# LastSchema.net
KiCad netlist of a schematic drawn in Altium Designer
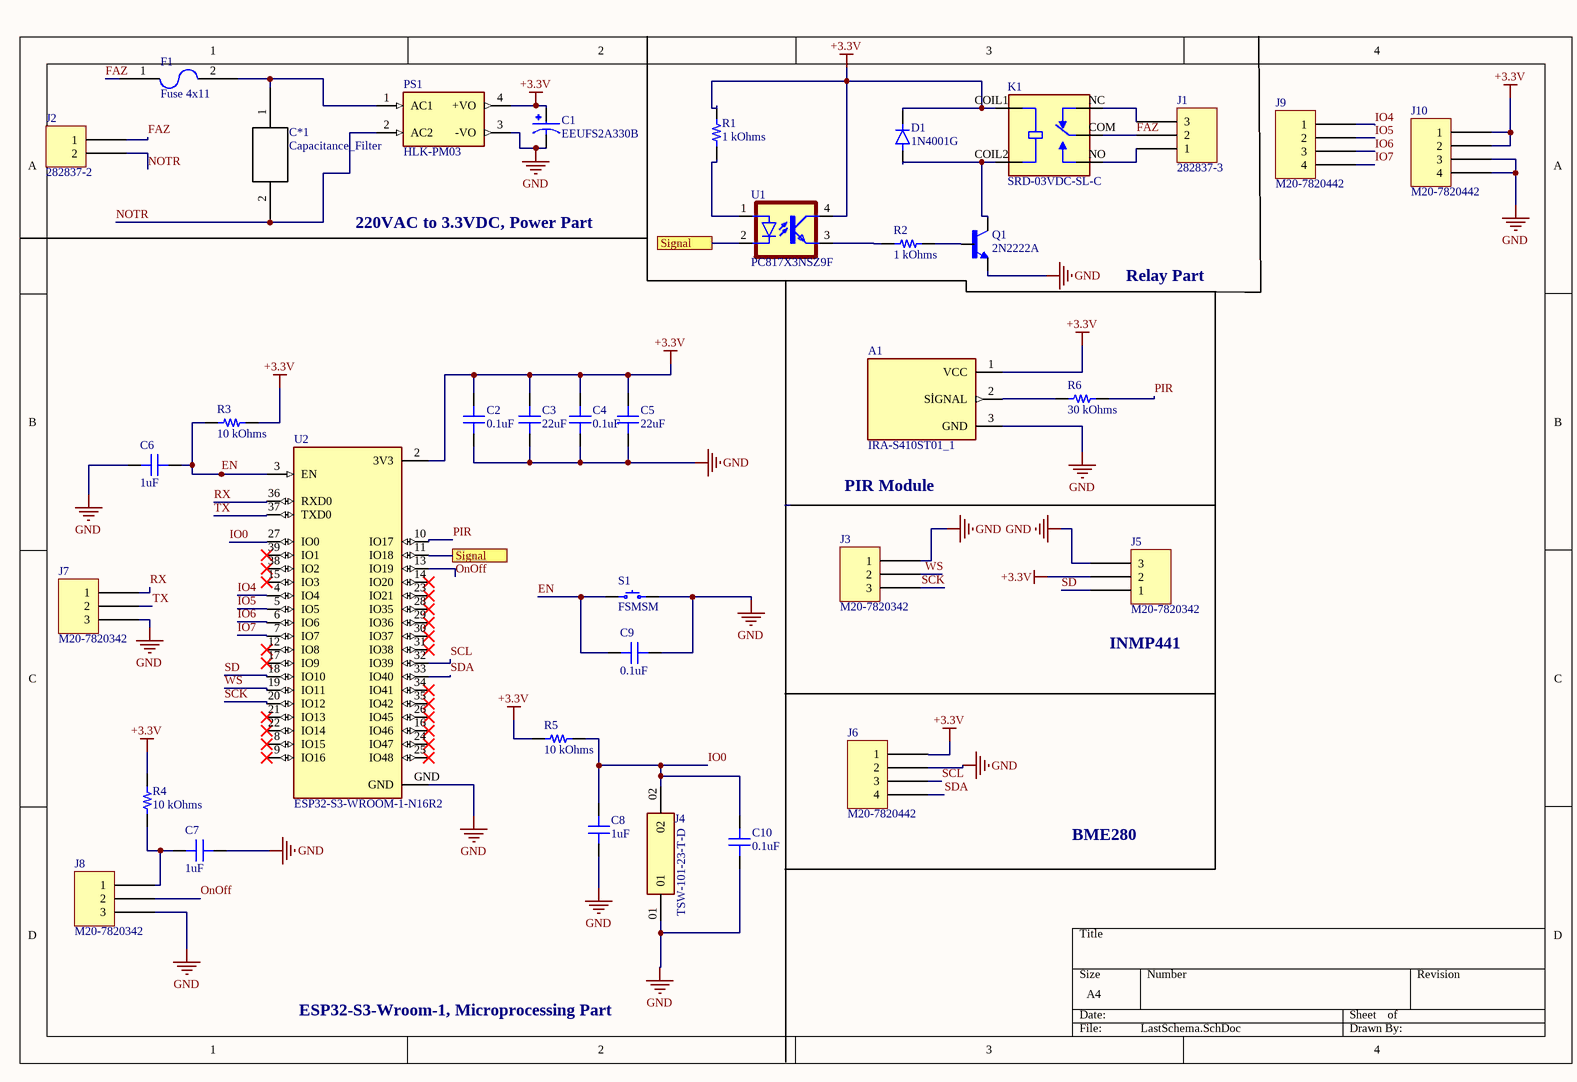
[diagram p0: LastSchema.SchDoc]

(export (version "E")
  (design (tool "Eeschema 10.0.6"))
  (components
    (comp (ref "A1")
      (value "IRA-S410ST01_1")
      (footprint "TO254P940H490-3 - duplicate")
      (description "Sensor PIR (Passive Infrared) Motion Sensing Radial, Metal Can, Lensed - 3 Lead")
      (fields (field (name "MP") "IRA-S410ST01") (field (name "MF") "Murata"))
      (libsource (lib "Integrated_Library1") (part "IRA-S410ST01_1"))
    )
    (comp (ref "C*1")
      (value "Capacitance_Filter")
      (footprint "Capacitance_Filter")
      (libsource (lib "Integrated_Library1") (part "Capacitance_Filter"))
    )
    (comp (ref "C1")
      (value "EEUFS2A330B")
      (footprint "CAPPRD500W60D800H1150")
      (description "CAP ALUM 33UF 20% 100V THRU HOLE")
      (fields (field (name "MF") "Panasonic"))
      (libsource (lib "Integrated_Library1") (part "EEUFS2A330B"))
    )
    (comp (ref "C2")
      (value "1 µF")
      (footprint "CAP 0603_1608")
      (description "CAP CER 1UF 16V X7R 0603")
      (fields
        (field (name "PART NUMBER") "C0603C105K4RACAUTO")
        (field (name "CAPACITANCE") "0.1uF")
        (field (name "MANUFACTURER") "KEMET")
      )
      (libsource (lib "Celestial Altium Library - altium_library") (part "Capacitor"))
    )
    (comp (ref "C3")
      (value "1 µF")
      (footprint "CAP 0603_1608")
      (description "CAP CER 1UF 16V X7R 0603")
      (fields
        (field (name "PART NUMBER") "C0603C105K4RACAUTO")
        (field (name "CAPACITANCE") "22uF")
        (field (name "MANUFACTURER") "KEMET")
      )
      (libsource (lib "Celestial Altium Library - altium_library") (part "Capacitor"))
    )
    (comp (ref "C4")
      (value "1 µF")
      (footprint "CAP 0603_1608")
      (description "CAP CER 1UF 16V X7R 0603")
      (fields
        (field (name "PART NUMBER") "C0603C105K4RACAUTO")
        (field (name "CAPACITANCE") "0.1uF")
        (field (name "MANUFACTURER") "KEMET")
      )
      (libsource (lib "Celestial Altium Library - altium_library") (part "Capacitor"))
    )
    (comp (ref "C5")
      (value "1 µF")
      (footprint "CAP 0603_1608")
      (description "CAP CER 1UF 16V X7R 0603")
      (fields
        (field (name "PART NUMBER") "C0603C105K4RACAUTO")
        (field (name "CAPACITANCE") "22uF")
        (field (name "MANUFACTURER") "KEMET")
      )
      (libsource (lib "Celestial Altium Library - altium_library") (part "Capacitor"))
    )
    (comp (ref "C6")
      (value "1 µF")
      (footprint "CAP 0603_1608")
      (description "CAP CER 1UF 16V X7R 0603")
      (fields
        (field (name "PART NUMBER") "C0603C105K4RACAUTO")
        (field (name "CAPACITANCE") "1uF")
        (field (name "MANUFACTURER") "KEMET")
      )
      (libsource (lib "Celestial Altium Library - altium_library") (part "Capacitor"))
    )
    (comp (ref "C7")
      (value "1 µF")
      (footprint "CAP 0603_1608")
      (description "CAP CER 1UF 16V X7R 0603")
      (fields
        (field (name "PART NUMBER") "C0603C105K4RACAUTO")
        (field (name "CAPACITANCE") "1uF")
        (field (name "MANUFACTURER") "KEMET")
      )
      (libsource (lib "Celestial Altium Library - altium_library") (part "Capacitor"))
    )
    (comp (ref "C8")
      (value "1 µF")
      (footprint "CAP 0603_1608")
      (description "CAP CER 1UF 16V X7R 0603")
      (fields
        (field (name "PART NUMBER") "C0603C105K4RACAUTO")
        (field (name "CAPACITANCE") "1uF")
        (field (name "MANUFACTURER") "KEMET")
      )
      (libsource (lib "Celestial Altium Library - altium_library") (part "Capacitor"))
    )
    (comp (ref "C9")
      (value "1 µF")
      (footprint "CAP 0603_1608")
      (description "CAP CER 1UF 16V X7R 0603")
      (fields
        (field (name "PART NUMBER") "C0603C105K4RACAUTO")
        (field (name "CAPACITANCE") "0.1uF")
        (field (name "MANUFACTURER") "KEMET")
      )
      (libsource (lib "Celestial Altium Library - altium_library") (part "Capacitor"))
    )
    (comp (ref "C10")
      (value "1 µF")
      (footprint "CAP 0603_1608")
      (description "CAP CER 1UF 16V X7R 0603")
      (fields
        (field (name "PART NUMBER") "C0603C105K4RACAUTO")
        (field (name "CAPACITANCE") "0.1uF")
        (field (name "MANUFACTURER") "KEMET")
      )
      (libsource (lib "Celestial Altium Library - altium_library") (part "Capacitor"))
    )
    (comp (ref "D1")
      (value "1N4001G")
      (footprint "DIOAD1036W78L470D235")
      (description "1A, 50V, Standard Recovery Rectifier")
      (fields (field (name "MF") "Taiwan Semiconductor"))
      (libsource (lib "Integrated_Library1") (part "1N4001G"))
    )
    (comp (ref "F1")
      (value "Fuse 4x11")
      (footprint "Fuse 4x11")
      (libsource (lib "Integrated_Library1") (part "Fuse 4x11"))
    )
    (comp (ref "J1")
      (value "282837-3")
      (footprint "TE 282837-3")
      (description "TERM BLK 3P SIDE ENT 5.08MM PCB")
      (fields (field (name "MANUFACTURER") "TE Connectivity AMP Connectors") (field (name "VOLTAGE") "300 V"))
      (libsource (lib "Celestial Altium Library - altium_library") (part "3 Pin"))
    )
    (comp (ref "J2")
      (value "282837-2")
      (footprint "TE 282837-2")
      (description "TERM BLK 2P SIDE ENT 5.08MM PCB")
      (fields (field (name "MANUFACTURER") "TE Connectivity AMP Connectors") (field (name "VOLTAGE") "300 V"))
      (libsource (lib "Celestial Altium Library - altium_library") (part "2 Pin"))
    )
    (comp (ref "J3")
      (value "M20-7820342")
      (footprint "HARWIN M20-7820345")
      (description "CONN RCPT 3POS 0.1 GOLD PCB")
      (fields (field (name "MANUFACTURER") "Harwin Inc."))
      (libsource (lib "") (part "3 Pin_1"))
    )
    (comp (ref "J4")
      (value "TSW-101-23-T-D")
      (footprint "SAMTEC_TSW-101-23-T-D")
      (description "TSW Series .100 Terminal Strip")
      (fields (field (name "MF") "Samtec"))
      (libsource (lib "Integrated_Library1") (part "TSW-101-23-T-D"))
    )
    (comp (ref "J5")
      (value "M20-7820342")
      (footprint "HARWIN M20-7820345")
      (description "CONN RCPT 3POS 0.1 GOLD PCB")
      (fields (field (name "MANUFACTURER") "Harwin Inc."))
      (libsource (lib "Celestial Altium Library - altium_library") (part "3 Pin"))
    )
    (comp (ref "J6")
      (value "M20-7820442")
      (footprint "HARWIN M20-7820445")
      (description "CONN RCPT 4POS 0.1 GOLD PCB")
      (fields (field (name "MANUFACTURER") "Harwin Inc."))
      (libsource (lib "Celestial Altium Library - altium_library") (part "4 Pin"))
    )
    (comp (ref "J7")
      (value "M20-7820342")
      (footprint "HARWIN M20-7820345")
      (description "CONN RCPT 3POS 0.1 GOLD PCB")
      (fields (field (name "MANUFACTURER") "Harwin Inc."))
      (libsource (lib "") (part "3 Pin_1"))
    )
    (comp (ref "J8")
      (value "M20-7820342")
      (footprint "HARWIN M20-7820345")
      (description "CONN RCPT 3POS 0.1 GOLD PCB")
      (fields (field (name "MANUFACTURER") "Harwin Inc."))
      (libsource (lib "") (part "3 Pin_1"))
    )
    (comp (ref "J9")
      (value "M20-7820442")
      (footprint "HARWIN M20-7820445")
      (description "CONN RCPT 4POS 0.1 GOLD PCB")
      (fields (field (name "MANUFACTURER") "Harwin Inc."))
      (libsource (lib "Celestial Altium Library - altium_library") (part "4 Pin"))
    )
    (comp (ref "J10")
      (value "M20-7820442")
      (footprint "HARWIN M20-7820445")
      (description "CONN RCPT 4POS 0.1 GOLD PCB")
      (fields (field (name "MANUFACTURER") "Harwin Inc."))
      (libsource (lib "Celestial Altium Library - altium_library") (part "4 Pin"))
    )
    (comp (ref "K1")
      (value "SRD-03VDC-SL-C")
      (footprint "RELAY_SRD-03VDC-SL-C")
      (description "Relays General Purpose Non Latching 3VDC SPDT 10A (250VAC) Max 5PIN")
      (fields (field (name "MF") "Songle Relay"))
      (libsource (lib "Integrated_Library1") (part "SRD-03VDC-SL-C"))
    )
    (comp (ref "PS1")
      (value "HLK-PM03")
      (footprint "CONV_HLK-PM03")
      (fields (field (name "MF") "Hi-link"))
      (libsource (lib "Integrated_Library1") (part "HLK-PM03"))
    )
    (comp (ref "Q1")
      (value "2N2222A")
      (footprint "TO92254P470H750-3")
      (description "Bipolar (BJT) Transistor NPN 40 V 600 mA 250MHz 625 mW Through Hole TO-92")
      (fields (field (name "MF") "Diotec Semiconductor"))
      (libsource (lib "Integrated_Library1") (part "2N2222A"))
    )
    (comp (ref "R1")
      (value "1 kOhms")
      (footprint "RES 0603_1608")
      (description "RES SMD 46.4K OHM 0.5% 1/5W 0603")
      (fields
        (field (name "PART NUMBER") "ERJ-PB3D4642V")
        (field (name "MANUFACTURER") "Panasonic Electronic Components")
      )
      (libsource (lib "Celestial Altium Library - altium_library") (part "Resistor"))
    )
    (comp (ref "R2")
      (value "1 kOhms")
      (footprint "RES 0603_1608")
      (description "RES SMD 46.4K OHM 0.5% 1/5W 0603")
      (fields
        (field (name "PART NUMBER") "ERJ-PB3D4642V")
        (field (name "MANUFACTURER") "Panasonic Electronic Components")
      )
      (libsource (lib "Celestial Altium Library - altium_library") (part "Resistor"))
    )
    (comp (ref "R3")
      (value "10 kOhms")
      (footprint "RES 0603_1608")
      (description "RES SMD 46.4K OHM 0.5% 1/5W 0603")
      (fields
        (field (name "PART NUMBER") "ERJ-PB3D4642V")
        (field (name "MANUFACTURER") "Panasonic Electronic Components")
      )
      (libsource (lib "Celestial Altium Library - altium_library") (part "Resistor"))
    )
    (comp (ref "R4")
      (value "10 kOhms")
      (footprint "RES 0603_1608")
      (description "RES SMD 46.4K OHM 0.5% 1/5W 0603")
      (fields
        (field (name "PART NUMBER") "ERJ-PB3D4642V")
        (field (name "MANUFACTURER") "Panasonic Electronic Components")
      )
      (libsource (lib "Celestial Altium Library - altium_library") (part "Resistor"))
    )
    (comp (ref "R5")
      (value "10 kOhms")
      (footprint "RES 0603_1608")
      (description "RES SMD 46.4K OHM 0.5% 1/5W 0603")
      (fields
        (field (name "PART NUMBER") "ERJ-PB3D4642V")
        (field (name "MANUFACTURER") "Panasonic Electronic Components")
      )
      (libsource (lib "Celestial Altium Library - altium_library") (part "Resistor"))
    )
    (comp (ref "R6")
      (value "30 kOhms")
      (footprint "RES 0603_1608")
      (description "RES 10K OHM 0.1% 1/16W 0603")
      (fields
        (field (name "PART NUMBER") "RNCS0603BKE10K0")
        (field (name "MANUFACTURER") "Stackpole Electronics Inc")
      )
      (libsource (lib "Celestial Altium Library - altium_library") (part "Resistor"))
    )
    (comp (ref "S1")
      (value "FSMSM")
      (footprint "TE FSMSMTR")
      (description "SWITCH TACTILE SPST-NO 0.05A 24V")
      (fields (field (name "MANUFACTURER") "TE Connectivity ALCOSWITCH Switches"))
      (libsource (lib "Celestial Altium Library - altium_library") (part "SPST-NO 2 PIN"))
    )
    (comp (ref "U1")
      (value "PC817X3NSZ9F")
      (footprint "DIL04")
      (description "Optoisolator Transistor Output 5000Vrms 1 Channel 4-DIP")
      (fields (field (name "MF") "Sharp Microelectronics"))
      (libsource (lib "Integrated_Library1") (part "PC817X3NSZ9F"))
    )
    (comp (ref "U2")
      (value "ESP32-S3-WROOM-1-N16R2")
      (footprint "XCVR_ESP32-S3-WROOM-1-N16R2")
      (description "Bluetooth, WiFi 802.11b/g/n, Bluetooth v5.0 Transceiver Module 2.4GHz PCB Trace Surface Mount")
      (fields (field (name "MF") "Espressif Systems") (field (name "MP") "ESP32S3WROOM1N16R2"))
      (libsource (lib "Integrated_Library1") (part "ESP32-S3-WROOM-1-N16R2"))
    )
  )
  (nets
    (net (code "1") (name "+3.3V") (class "Default")
      (node (ref "A1") (pin "1") (pinfunction "VCC_1") (pintype "power_in"))
      (node (ref "C1") (pin "P") (pinfunction "P_P") (pintype "passive"))
      (node (ref "C2") (pin "1") (pinfunction "1_1") (pintype "passive"))
      (node (ref "C3") (pin "1") (pinfunction "1_1") (pintype "passive"))
      (node (ref "C4") (pin "1") (pinfunction "1_1") (pintype "passive"))
      (node (ref "C5") (pin "1") (pinfunction "1_1") (pintype "passive"))
      (node (ref "D1") (pin "C") (pinfunction "K_C") (pintype "passive"))
      (node (ref "J10") (pin "1") (pinfunction "1_1") (pintype "passive"))
      (node (ref "J10") (pin "2") (pinfunction "2_2") (pintype "passive"))
      (node (ref "J5") (pin "2") (pinfunction "2_2") (pintype "passive"))
      (node (ref "J6") (pin "1") (pinfunction "1_1") (pintype "passive"))
      (node (ref "K1") (pin "COIL1") (pinfunction "COIL1_COIL1") (pintype "passive"))
      (node (ref "PS1") (pin "4") (pinfunction "+VO_4") (pintype "output"))
      (node (ref "R1") (pin "2") (pinfunction "2_2") (pintype "passive"))
      (node (ref "R3") (pin "1") (pinfunction "1_1") (pintype "passive"))
      (node (ref "R4") (pin "1") (pinfunction "1_1") (pintype "passive"))
      (node (ref "R5") (pin "2") (pinfunction "2_2") (pintype "passive"))
      (node (ref "U1") (pin "4") (pinfunction "COL_4") (pintype "passive"))
      (node (ref "U2") (pin "2") (pinfunction "3V3_2") (pintype "power_in"))
    )
    (net (code "2") (name "/EN") (class "Default")
      (node (ref "C6") (pin "2") (pinfunction "2_2") (pintype "passive"))
      (node (ref "C9") (pin "2") (pinfunction "2_2") (pintype "passive"))
      (node (ref "R3") (pin "2") (pinfunction "2_2") (pintype "passive"))
      (node (ref "S1") (pin "1") (pinfunction "1_1") (pintype "passive"))
      (node (ref "U2") (pin "3") (pinfunction "EN_3") (pintype "input"))
    )
    (net (code "3") (name "/FAZ") (class "Default")
      (node (ref "F1") (pin "1") (pintype "passive"))
      (node (ref "J1") (pin "2") (pinfunction "2_2") (pintype "passive"))
      (node (ref "J2") (pin "1") (pinfunction "1_1") (pintype "passive"))
      (node (ref "K1") (pin "COM") (pinfunction "COM_COM") (pintype "passive"))
    )
    (net (code "4") (name "/IO0") (class "Default")
      (node (ref "C10") (pin "1") (pinfunction "1_1") (pintype "passive"))
      (node (ref "C8") (pin "2") (pinfunction "2_2") (pintype "passive"))
      (node (ref "J4") (pin "02") (pinfunction "02_02") (pintype "passive"))
      (node (ref "R5") (pin "1") (pinfunction "1_1") (pintype "passive"))
      (node (ref "U2") (pin "27") (pinfunction "IO0_27") (pintype "bidirectional"))
    )
    (net (code "5") (name "/IO4") (class "Default")
      (node (ref "J9") (pin "1") (pinfunction "1_1") (pintype "passive"))
      (node (ref "U2") (pin "4") (pinfunction "IO4_4") (pintype "bidirectional"))
    )
    (net (code "6") (name "/IO5") (class "Default")
      (node (ref "J9") (pin "2") (pinfunction "2_2") (pintype "passive"))
      (node (ref "U2") (pin "5") (pinfunction "IO5_5") (pintype "bidirectional"))
    )
    (net (code "7") (name "/IO6") (class "Default")
      (node (ref "J9") (pin "3") (pinfunction "3_3") (pintype "passive"))
      (node (ref "U2") (pin "6") (pinfunction "IO6_6") (pintype "bidirectional"))
    )
    (net (code "8") (name "/IO7") (class "Default")
      (node (ref "J9") (pin "4") (pinfunction "4_4") (pintype "passive"))
      (node (ref "U2") (pin "7") (pinfunction "IO7_7") (pintype "bidirectional"))
    )
    (net (code "9") (name "/NOTR") (class "Default")
      (node (ref "C*1") (pin "2") (pintype "passive"))
      (node (ref "J2") (pin "2") (pinfunction "2_2") (pintype "passive"))
      (node (ref "PS1") (pin "2") (pinfunction "AC2_2") (pintype "input"))
    )
    (net (code "10") (name "/OnOff") (class "Default")
      (node (ref "J8") (pin "2") (pinfunction "2_2") (pintype "passive"))
      (node (ref "U2") (pin "13") (pinfunction "IO19_13") (pintype "bidirectional"))
    )
    (net (code "11") (name "/PIR") (class "Default")
      (node (ref "R6") (pin "2") (pinfunction "2_2") (pintype "passive"))
      (node (ref "U2") (pin "10") (pinfunction "IO17_10") (pintype "bidirectional"))
    )
    (net (code "12") (name "/RX") (class "Default")
      (node (ref "J7") (pin "1") (pinfunction "1_1") (pintype "passive"))
      (node (ref "U2") (pin "36") (pinfunction "RXD0_36") (pintype "bidirectional"))
    )
    (net (code "13") (name "/SCK") (class "Default")
      (node (ref "J3") (pin "3") (pinfunction "3_3") (pintype "passive"))
      (node (ref "U2") (pin "20") (pinfunction "IO12_20") (pintype "bidirectional"))
    )
    (net (code "14") (name "/SCL") (class "Default")
      (node (ref "J6") (pin "3") (pinfunction "3_3") (pintype "passive"))
      (node (ref "U2") (pin "32") (pinfunction "IO39_32") (pintype "bidirectional"))
    )
    (net (code "15") (name "/SD") (class "Default")
      (node (ref "J5") (pin "1") (pinfunction "1_1") (pintype "passive"))
      (node (ref "U2") (pin "18") (pinfunction "IO10_18") (pintype "bidirectional"))
    )
    (net (code "16") (name "/SDA") (class "Default")
      (node (ref "J6") (pin "4") (pinfunction "4_4") (pintype "passive"))
      (node (ref "U2") (pin "33") (pinfunction "IO40_33") (pintype "bidirectional"))
    )
    (net (code "17") (name "/Signal") (class "Default")
      (node (ref "U1") (pin "2") (pinfunction "C_2") (pintype "passive"))
      (node (ref "U2") (pin "11") (pinfunction "IO18_11") (pintype "bidirectional"))
    )
    (net (code "18") (name "/TX") (class "Default")
      (node (ref "J7") (pin "2") (pinfunction "2_2") (pintype "passive"))
      (node (ref "U2") (pin "37") (pinfunction "TXD0_37") (pintype "bidirectional"))
    )
    (net (code "19") (name "/WS") (class "Default")
      (node (ref "J3") (pin "2") (pinfunction "2_2") (pintype "passive"))
      (node (ref "U2") (pin "19") (pinfunction "IO11_19") (pintype "bidirectional"))
    )
    (net (code "20") (name "GND") (class "Default")
      (node (ref "A1") (pin "3") (pinfunction "GND_3") (pintype "power_in"))
      (node (ref "C1") (pin "N") (pinfunction "N_N") (pintype "passive"))
      (node (ref "C10") (pin "2") (pinfunction "2_2") (pintype "passive"))
      (node (ref "C2") (pin "2") (pinfunction "2_2") (pintype "passive"))
      (node (ref "C3") (pin "2") (pinfunction "2_2") (pintype "passive"))
      (node (ref "C4") (pin "2") (pinfunction "2_2") (pintype "passive"))
      (node (ref "C5") (pin "2") (pinfunction "2_2") (pintype "passive"))
      (node (ref "C6") (pin "1") (pinfunction "1_1") (pintype "passive"))
      (node (ref "C7") (pin "2") (pinfunction "2_2") (pintype "passive"))
      (node (ref "C8") (pin "1") (pinfunction "1_1") (pintype "passive"))
      (node (ref "C9") (pin "1") (pinfunction "1_1") (pintype "passive"))
      (node (ref "J10") (pin "3") (pinfunction "3_3") (pintype "passive"))
      (node (ref "J10") (pin "4") (pinfunction "4_4") (pintype "passive"))
      (node (ref "J3") (pin "1") (pinfunction "1_1") (pintype "passive"))
      (node (ref "J4") (pin "01") (pinfunction "01_01") (pintype "passive"))
      (node (ref "J5") (pin "3") (pinfunction "3_3") (pintype "passive"))
      (node (ref "J6") (pin "2") (pinfunction "2_2") (pintype "passive"))
      (node (ref "J7") (pin "3") (pinfunction "3_3") (pintype "passive"))
      (node (ref "J8") (pin "3") (pinfunction "3_3") (pintype "passive"))
      (node (ref "PS1") (pin "3") (pinfunction "-VO_3") (pintype "output"))
      (node (ref "Q1") (pin "1") (pinfunction "E_1") (pintype "passive"))
      (node (ref "S1") (pin "2") (pinfunction "2_2") (pintype "passive"))
      (node (ref "U2") (pin "GND") (pinfunction "GND_GND") (pintype "power_in"))
    )
    (net (code "21") (name "Net-(A1-SİGNAL)") (class "Default")
      (node (ref "A1") (pin "2") (pinfunction "SİGNAL_2") (pintype "output"))
      (node (ref "R6") (pin "1") (pinfunction "1_1") (pintype "passive"))
    )
    (net (code "22") (name "Net-(C7-Pad1)") (class "Default")
      (node (ref "C7") (pin "1") (pinfunction "1_1") (pintype "passive"))
      (node (ref "J8") (pin "1") (pinfunction "1_1") (pintype "passive"))
      (node (ref "R4") (pin "2") (pinfunction "2_2") (pintype "passive"))
    )
    (net (code "23") (name "Net-(J1-Pad1)") (class "Default")
      (node (ref "J1") (pin "1") (pinfunction "1_1") (pintype "passive"))
      (node (ref "K1") (pin "NO") (pinfunction "NO_NO") (pintype "passive"))
    )
    (net (code "24") (name "Net-(J1-Pad3)") (class "Default")
      (node (ref "J1") (pin "3") (pinfunction "3_3") (pintype "passive"))
      (node (ref "K1") (pin "NC") (pinfunction "NC_NC") (pintype "passive"))
    )
    (net (code "25") (name "Net-(PS1-AC1)") (class "Default")
      (node (ref "C*1") (pin "1") (pintype "passive"))
      (node (ref "F1") (pin "2") (pintype "passive"))
      (node (ref "PS1") (pin "1") (pinfunction "AC1_1") (pintype "input"))
    )
    (net (code "26") (name "Net-(Q1-B)") (class "Default")
      (node (ref "Q1") (pin "2") (pinfunction "B_2") (pintype "passive"))
      (node (ref "R2") (pin "2") (pinfunction "2_2") (pintype "passive"))
    )
    (net (code "27") (name "Net-(Q1-C)") (class "Default")
      (node (ref "D1") (pin "A") (pinfunction "A_A") (pintype "passive"))
      (node (ref "K1") (pin "COIL2") (pinfunction "COIL2_COIL2") (pintype "passive"))
      (node (ref "Q1") (pin "3") (pinfunction "C_3") (pintype "passive"))
    )
    (net (code "28") (name "Net-(U1-A)") (class "Default")
      (node (ref "R1") (pin "1") (pinfunction "1_1") (pintype "passive"))
      (node (ref "U1") (pin "1") (pinfunction "A_1") (pintype "passive"))
    )
    (net (code "29") (name "Net-(U1-EMIT)") (class "Default")
      (node (ref "R2") (pin "1") (pinfunction "1_1") (pintype "passive"))
      (node (ref "U1") (pin "3") (pinfunction "EMIT_3") (pintype "passive"))
    )
    (net (code "30") (name "unconnected-(U2-IO1-Pad39)") (class "Default")
      (node (ref "U2") (pin "39") (pinfunction "IO1_39") (pintype "bidirectional+no_connect"))
    )
    (net (code "31") (name "unconnected-(U2-IO2-Pad38)") (class "Default")
      (node (ref "U2") (pin "38") (pinfunction "IO2_38") (pintype "bidirectional+no_connect"))
    )
    (net (code "32") (name "unconnected-(U2-IO3-Pad15)") (class "Default")
      (node (ref "U2") (pin "15") (pinfunction "IO3_15") (pintype "bidirectional+no_connect"))
    )
    (net (code "33") (name "unconnected-(U2-IO8-Pad12)") (class "Default")
      (node (ref "U2") (pin "12") (pinfunction "IO8_12") (pintype "bidirectional+no_connect"))
    )
    (net (code "34") (name "unconnected-(U2-IO9-Pad17)") (class "Default")
      (node (ref "U2") (pin "17") (pinfunction "IO9_17") (pintype "bidirectional+no_connect"))
    )
    (net (code "35") (name "unconnected-(U2-IO13-Pad21)") (class "Default")
      (node (ref "U2") (pin "21") (pinfunction "IO13_21") (pintype "bidirectional+no_connect"))
    )
    (net (code "36") (name "unconnected-(U2-IO14-Pad22)") (class "Default")
      (node (ref "U2") (pin "22") (pinfunction "IO14_22") (pintype "bidirectional+no_connect"))
    )
    (net (code "37") (name "unconnected-(U2-IO15-Pad8)") (class "Default")
      (node (ref "U2") (pin "8") (pinfunction "IO15_8") (pintype "bidirectional+no_connect"))
    )
    (net (code "38") (name "unconnected-(U2-IO16-Pad9)") (class "Default")
      (node (ref "U2") (pin "9") (pinfunction "IO16_9") (pintype "bidirectional+no_connect"))
    )
    (net (code "39") (name "unconnected-(U2-IO20-Pad14)") (class "Default")
      (node (ref "U2") (pin "14") (pinfunction "IO20_14") (pintype "bidirectional+no_connect"))
    )
    (net (code "40") (name "unconnected-(U2-IO21-Pad23)") (class "Default")
      (node (ref "U2") (pin "23") (pinfunction "IO21_23") (pintype "bidirectional+no_connect"))
    )
    (net (code "41") (name "unconnected-(U2-IO35-Pad28)") (class "Default")
      (node (ref "U2") (pin "28") (pinfunction "IO35_28") (pintype "bidirectional+no_connect"))
    )
    (net (code "42") (name "unconnected-(U2-IO36-Pad29)") (class "Default")
      (node (ref "U2") (pin "29") (pinfunction "IO36_29") (pintype "bidirectional+no_connect"))
    )
    (net (code "43") (name "unconnected-(U2-IO37-Pad30)") (class "Default")
      (node (ref "U2") (pin "30") (pinfunction "IO37_30") (pintype "bidirectional+no_connect"))
    )
    (net (code "44") (name "unconnected-(U2-IO38-Pad31)") (class "Default")
      (node (ref "U2") (pin "31") (pinfunction "IO38_31") (pintype "bidirectional+no_connect"))
    )
    (net (code "45") (name "unconnected-(U2-IO41-Pad34)") (class "Default")
      (node (ref "U2") (pin "34") (pinfunction "IO41_34") (pintype "bidirectional+no_connect"))
    )
    (net (code "46") (name "unconnected-(U2-IO42-Pad35)") (class "Default")
      (node (ref "U2") (pin "35") (pinfunction "IO42_35") (pintype "bidirectional+no_connect"))
    )
    (net (code "47") (name "unconnected-(U2-IO45-Pad26)") (class "Default")
      (node (ref "U2") (pin "26") (pinfunction "IO45_26") (pintype "bidirectional+no_connect"))
    )
    (net (code "48") (name "unconnected-(U2-IO46-Pad16)") (class "Default")
      (node (ref "U2") (pin "16") (pinfunction "IO46_16") (pintype "bidirectional+no_connect"))
    )
    (net (code "49") (name "unconnected-(U2-IO47-Pad24)") (class "Default")
      (node (ref "U2") (pin "24") (pinfunction "IO47_24") (pintype "bidirectional+no_connect"))
    )
    (net (code "50") (name "unconnected-(U2-IO48-Pad25)") (class "Default")
      (node (ref "U2") (pin "25") (pinfunction "IO48_25") (pintype "bidirectional+no_connect"))
    )
  )
)
